# USB_Hub.net
KiCad netlist of a schematic drawn in EasyEDA Pro
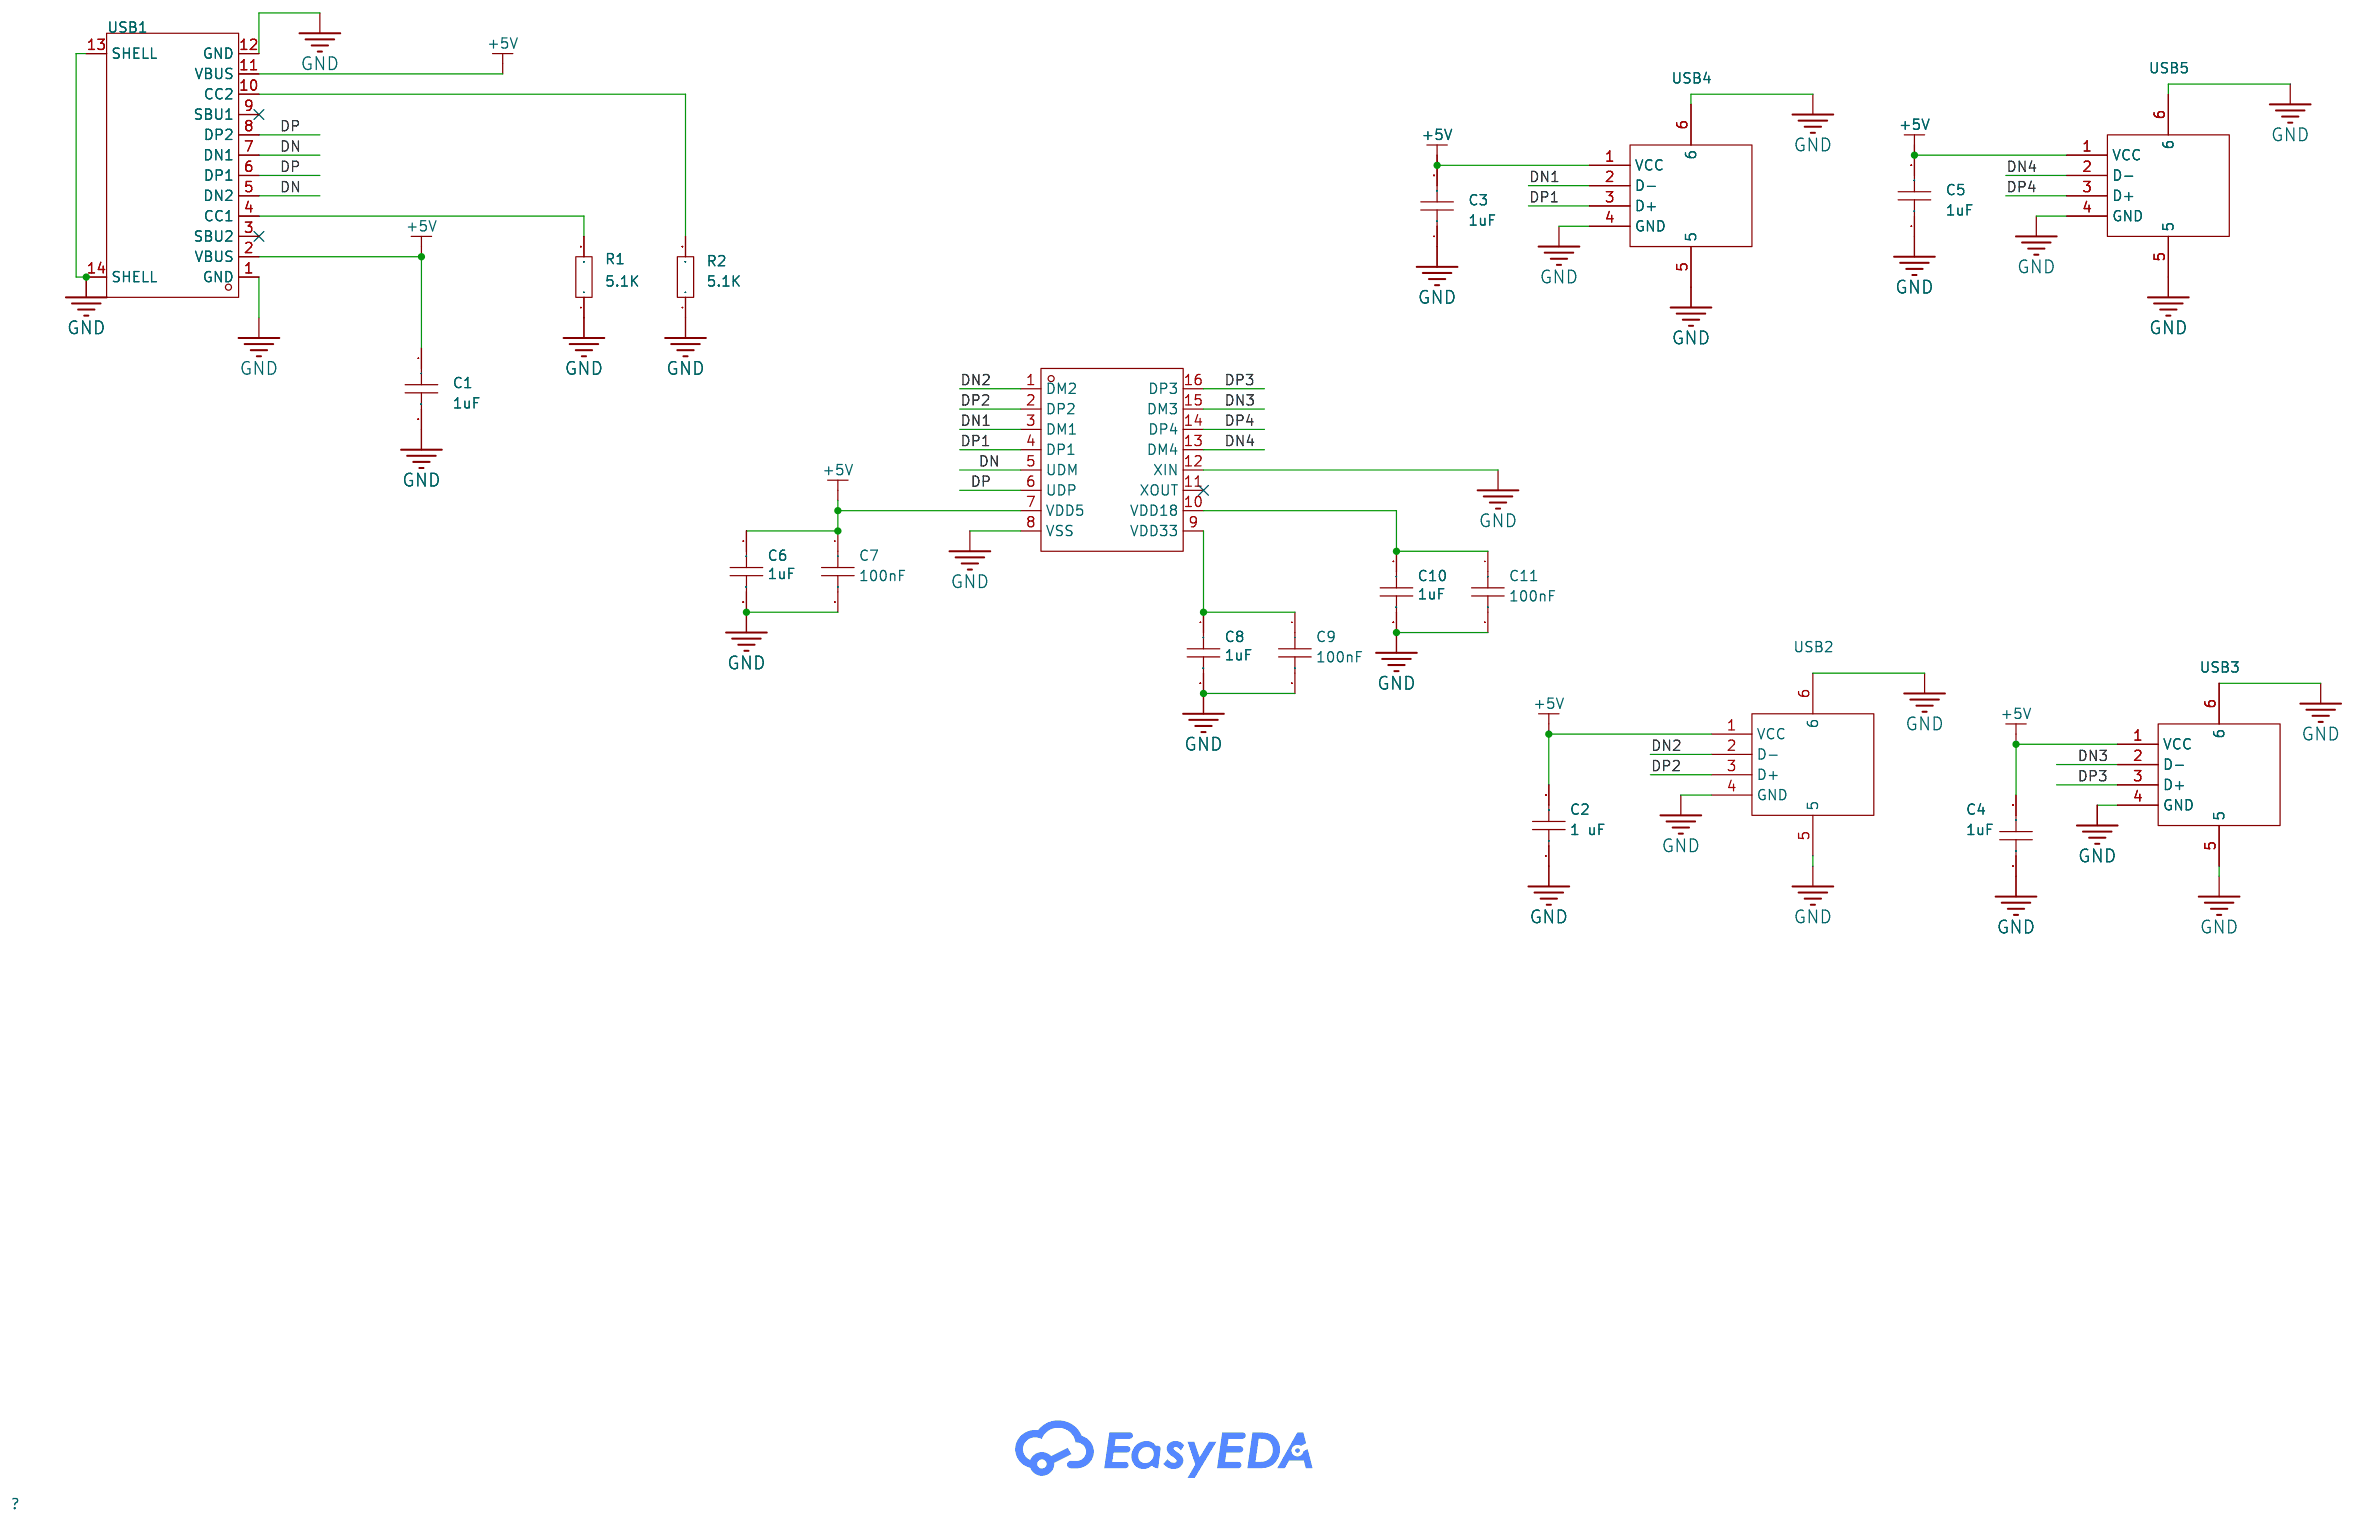
[diagram p0: schematic sheet]

(export (version "E")
  (design (tool "Eeschema 10.0.6"))
  (components
    (comp (ref "C1")
      (value "100nF")
      (footprint "easyedapro:C0603")
      (libsource (lib "easyedapro") (part "CAP"))
    )
    (comp (ref "C2")
      (value "1 uF")
      (footprint "easyedapro:C0603")
      (libsource (lib "easyedapro") (part "CAP"))
    )
    (comp (ref "C3")
      (value "100nF")
      (footprint "easyedapro:C0603")
      (libsource (lib "easyedapro") (part "CAP"))
    )
    (comp (ref "C4")
      (value "100nF")
      (footprint "easyedapro:C0603")
      (libsource (lib "easyedapro") (part "CAP"))
    )
    (comp (ref "C5")
      (value "100nF")
      (footprint "easyedapro:C0603")
      (libsource (lib "easyedapro") (part "CAP"))
    )
    (comp (ref "C6")
      (value "100nF")
      (footprint "easyedapro:C0603")
      (libsource (lib "easyedapro") (part "CAP"))
    )
    (comp (ref "C7")
      (value "100nF")
      (footprint "easyedapro:C0603")
      (libsource (lib "easyedapro") (part "CAP"))
    )
    (comp (ref "C8")
      (value "100nF")
      (footprint "easyedapro:C0603")
      (libsource (lib "easyedapro") (part "CAP"))
    )
    (comp (ref "C9")
      (value "100nF")
      (footprint "easyedapro:C0603")
      (libsource (lib "easyedapro") (part "CAP"))
    )
    (comp (ref "C10")
      (value "100nF")
      (footprint "easyedapro:C0603")
      (libsource (lib "easyedapro") (part "CAP"))
    )
    (comp (ref "C11")
      (value "100nF")
      (footprint "easyedapro:C0603")
      (libsource (lib "easyedapro") (part "CAP"))
    )
    (comp (ref "R1") (value "10K") (footprint "easyedapro:R0603") (libsource (lib "easyedapro") (part "Res")))
    (comp (ref "R2") (value "10K") (footprint "easyedapro:R0603") (libsource (lib "easyedapro") (part "Res")))
    (comp (ref "U1")
      (value "SL2.1s")
      (footprint "easyedapro:SSOP-16_L4.6-W2.6-P0.53-LS4.0-BL")
      (fields (field (name "Manufacturer") "CoreChips(和芯润德)"))
      (libsource (lib "easyedapro") (part "SL2.1S"))
    )
    (comp (ref "USB1")
      (value "TYPE-C 16PIN 2MD(073)")
      (footprint "easyedapro:USB-C-SMD_TYPE-C-6PIN-2MD-073")
      (fields (field (name "Manufacturer") "SHOU HAN(首韩)"))
      (libsource (lib "easyedapro") (part "TYPE-C 16PIN 2MD(073)"))
    )
    (comp (ref "USB2")
      (value "10.0 QHHTZB6.3")
      (footprint "easyedapro:USB-A-TH_10.0QHHTZB6.3")
      (fields (field (name "Manufacturer") "SHOU HAN(首韩)"))
      (libsource (lib "easyedapro") (part "10.0 QHHTZB6.3"))
    )
    (comp (ref "USB3")
      (value "10.0 QHHTZB6.3")
      (footprint "easyedapro:USB-A-TH_10.0QHHTZB6.3")
      (fields (field (name "Manufacturer") "SHOU HAN(首韩)"))
      (libsource (lib "easyedapro") (part "10.0 QHHTZB6.3"))
    )
    (comp (ref "USB4")
      (value "10.0 QHHTZB6.3")
      (footprint "easyedapro:USB-A-TH_10.0QHHTZB6.3")
      (fields (field (name "Manufacturer") "SHOU HAN(首韩)"))
      (libsource (lib "easyedapro") (part "10.0 QHHTZB6.3"))
    )
    (comp (ref "USB5")
      (value "10.0 QHHTZB6.3")
      (footprint "easyedapro:USB-A-TH_10.0QHHTZB6.3")
      (fields (field (name "Manufacturer") "SHOU HAN(首韩)"))
      (libsource (lib "easyedapro") (part "10.0 QHHTZB6.3"))
    )
  )
  (nets
    (net (code "1") (name "+5V") (class "Default")
      (node (ref "C1") (pin "1") (pinfunction "1_1") (pintype "input"))
      (node (ref "C2") (pin "2") (pinfunction "2_2") (pintype "input"))
      (node (ref "C3") (pin "2") (pinfunction "2_2") (pintype "input"))
      (node (ref "C4") (pin "2") (pinfunction "2_2") (pintype "input"))
      (node (ref "C5") (pin "2") (pinfunction "2_2") (pintype "input"))
      (node (ref "C6") (pin "1") (pinfunction "1_1") (pintype "input"))
      (node (ref "C7") (pin "1") (pinfunction "1_1") (pintype "input"))
      (node (ref "U1") (pin "7") (pinfunction "VDD5_7") (pintype "unspecified"))
      (node (ref "USB1") (pin "11") (pinfunction "VBUS_11") (pintype "unspecified"))
      (node (ref "USB1") (pin "2") (pinfunction "VBUS_2") (pintype "unspecified"))
      (node (ref "USB2") (pin "1") (pinfunction "VCC_1") (pintype "unspecified"))
      (node (ref "USB3") (pin "1") (pinfunction "VCC_1") (pintype "unspecified"))
      (node (ref "USB4") (pin "1") (pinfunction "VCC_1") (pintype "unspecified"))
      (node (ref "USB5") (pin "1") (pinfunction "VCC_1") (pintype "unspecified"))
    )
    (net (code "2") (name "/DN") (class "Default")
      (node (ref "U1") (pin "5") (pinfunction "UDM_5") (pintype "unspecified"))
      (node (ref "USB1") (pin "5") (pinfunction "DN2_5") (pintype "unspecified"))
      (node (ref "USB1") (pin "7") (pinfunction "DN1_7") (pintype "unspecified"))
    )
    (net (code "3") (name "/DN1") (class "Default")
      (node (ref "U1") (pin "3") (pinfunction "DM1_3") (pintype "unspecified"))
      (node (ref "USB4") (pin "2") (pinfunction "D-_2") (pintype "unspecified"))
    )
    (net (code "4") (name "/DN2") (class "Default")
      (node (ref "U1") (pin "1") (pinfunction "DM2_1") (pintype "unspecified"))
      (node (ref "USB2") (pin "2") (pinfunction "D-_2") (pintype "unspecified"))
    )
    (net (code "5") (name "/DN3") (class "Default")
      (node (ref "U1") (pin "15") (pinfunction "DM3_15") (pintype "unspecified"))
      (node (ref "USB3") (pin "2") (pinfunction "D-_2") (pintype "unspecified"))
    )
    (net (code "6") (name "/DN4") (class "Default")
      (node (ref "U1") (pin "13") (pinfunction "DM4_13") (pintype "unspecified"))
      (node (ref "USB5") (pin "2") (pinfunction "D-_2") (pintype "unspecified"))
    )
    (net (code "7") (name "/DP") (class "Default")
      (node (ref "U1") (pin "6") (pinfunction "UDP_6") (pintype "unspecified"))
      (node (ref "USB1") (pin "6") (pinfunction "DP1_6") (pintype "unspecified"))
      (node (ref "USB1") (pin "8") (pinfunction "DP2_8") (pintype "unspecified"))
    )
    (net (code "8") (name "/DP1") (class "Default")
      (node (ref "U1") (pin "4") (pinfunction "DP1_4") (pintype "unspecified"))
      (node (ref "USB4") (pin "3") (pinfunction "D+_3") (pintype "unspecified"))
    )
    (net (code "9") (name "/DP2") (class "Default")
      (node (ref "U1") (pin "2") (pinfunction "DP2_2") (pintype "unspecified"))
      (node (ref "USB2") (pin "3") (pinfunction "D+_3") (pintype "unspecified"))
    )
    (net (code "10") (name "/DP3") (class "Default")
      (node (ref "U1") (pin "16") (pinfunction "DP3_16") (pintype "unspecified"))
      (node (ref "USB3") (pin "3") (pinfunction "D+_3") (pintype "unspecified"))
    )
    (net (code "11") (name "/DP4") (class "Default")
      (node (ref "U1") (pin "14") (pinfunction "DP4_14") (pintype "unspecified"))
      (node (ref "USB5") (pin "3") (pinfunction "D+_3") (pintype "unspecified"))
    )
    (net (code "12") (name "GND") (class "Default")
      (node (ref "C1") (pin "2") (pinfunction "2_2") (pintype "input"))
      (node (ref "C10") (pin "2") (pinfunction "2_2") (pintype "input"))
      (node (ref "C11") (pin "2") (pinfunction "2_2") (pintype "input"))
      (node (ref "C2") (pin "1") (pinfunction "1_1") (pintype "input"))
      (node (ref "C3") (pin "1") (pinfunction "1_1") (pintype "input"))
      (node (ref "C4") (pin "1") (pinfunction "1_1") (pintype "input"))
      (node (ref "C5") (pin "1") (pinfunction "1_1") (pintype "input"))
      (node (ref "C6") (pin "2") (pinfunction "2_2") (pintype "input"))
      (node (ref "C7") (pin "2") (pinfunction "2_2") (pintype "input"))
      (node (ref "C8") (pin "2") (pinfunction "2_2") (pintype "input"))
      (node (ref "C9") (pin "2") (pinfunction "2_2") (pintype "input"))
      (node (ref "R1") (pin "1") (pinfunction "1_1") (pintype "input"))
      (node (ref "R2") (pin "1") (pinfunction "1_1") (pintype "input"))
      (node (ref "U1") (pin "12") (pinfunction "XIN_12") (pintype "unspecified"))
      (node (ref "U1") (pin "8") (pinfunction "VSS_8") (pintype "unspecified"))
      (node (ref "USB1") (pin "1") (pinfunction "GND_1") (pintype "unspecified"))
      (node (ref "USB1") (pin "12") (pinfunction "GND_12") (pintype "unspecified"))
      (node (ref "USB1") (pin "13") (pinfunction "SHELL_13") (pintype "unspecified"))
      (node (ref "USB1") (pin "14") (pinfunction "SHELL_14") (pintype "unspecified"))
      (node (ref "USB2") (pin "4") (pinfunction "GND_4") (pintype "unspecified"))
      (node (ref "USB2") (pin "5") (pinfunction "5_5") (pintype "unspecified"))
      (node (ref "USB2") (pin "6") (pinfunction "6_6") (pintype "unspecified"))
      (node (ref "USB3") (pin "4") (pinfunction "GND_4") (pintype "unspecified"))
      (node (ref "USB3") (pin "5") (pinfunction "5_5") (pintype "unspecified"))
      (node (ref "USB3") (pin "6") (pinfunction "6_6") (pintype "unspecified"))
      (node (ref "USB4") (pin "4") (pinfunction "GND_4") (pintype "unspecified"))
      (node (ref "USB4") (pin "5") (pinfunction "5_5") (pintype "unspecified"))
      (node (ref "USB4") (pin "6") (pinfunction "6_6") (pintype "unspecified"))
      (node (ref "USB5") (pin "4") (pinfunction "GND_4") (pintype "unspecified"))
      (node (ref "USB5") (pin "5") (pinfunction "5_5") (pintype "unspecified"))
      (node (ref "USB5") (pin "6") (pinfunction "6_6") (pintype "unspecified"))
    )
    (net (code "13") (name "Net-(U1-VDD18)") (class "Default")
      (node (ref "C10") (pin "1") (pinfunction "1_1") (pintype "input"))
      (node (ref "C11") (pin "1") (pinfunction "1_1") (pintype "input"))
      (node (ref "U1") (pin "10") (pinfunction "VDD18_10") (pintype "unspecified"))
    )
    (net (code "14") (name "Net-(U1-VDD33)") (class "Default")
      (node (ref "C8") (pin "1") (pinfunction "1_1") (pintype "input"))
      (node (ref "C9") (pin "1") (pinfunction "1_1") (pintype "input"))
      (node (ref "U1") (pin "9") (pinfunction "VDD33_9") (pintype "unspecified"))
    )
    (net (code "15") (name "Net-(USB1-CC1)") (class "Default")
      (node (ref "R1") (pin "2") (pinfunction "2_2") (pintype "input"))
      (node (ref "USB1") (pin "4") (pinfunction "CC1_4") (pintype "unspecified"))
    )
    (net (code "16") (name "Net-(USB1-CC2)") (class "Default")
      (node (ref "R2") (pin "2") (pinfunction "2_2") (pintype "input"))
      (node (ref "USB1") (pin "10") (pinfunction "CC2_10") (pintype "unspecified"))
    )
    (net (code "17") (name "unconnected-(U1-XOUT-Pad11)") (class "Default")
      (node (ref "U1") (pin "11") (pinfunction "XOUT_11") (pintype "unspecified+no_connect"))
    )
    (net (code "18") (name "unconnected-(USB1-SBU1-Pad9)") (class "Default")
      (node (ref "USB1") (pin "9") (pinfunction "SBU1_9") (pintype "unspecified+no_connect"))
    )
    (net (code "19") (name "unconnected-(USB1-SBU2-Pad3)") (class "Default")
      (node (ref "USB1") (pin "3") (pinfunction "SBU2_3") (pintype "unspecified+no_connect"))
    )
  )
)
